# rw-directish-17mm-mk-1_6.net
KiCad netlist of a schematic drawn in EAGLE
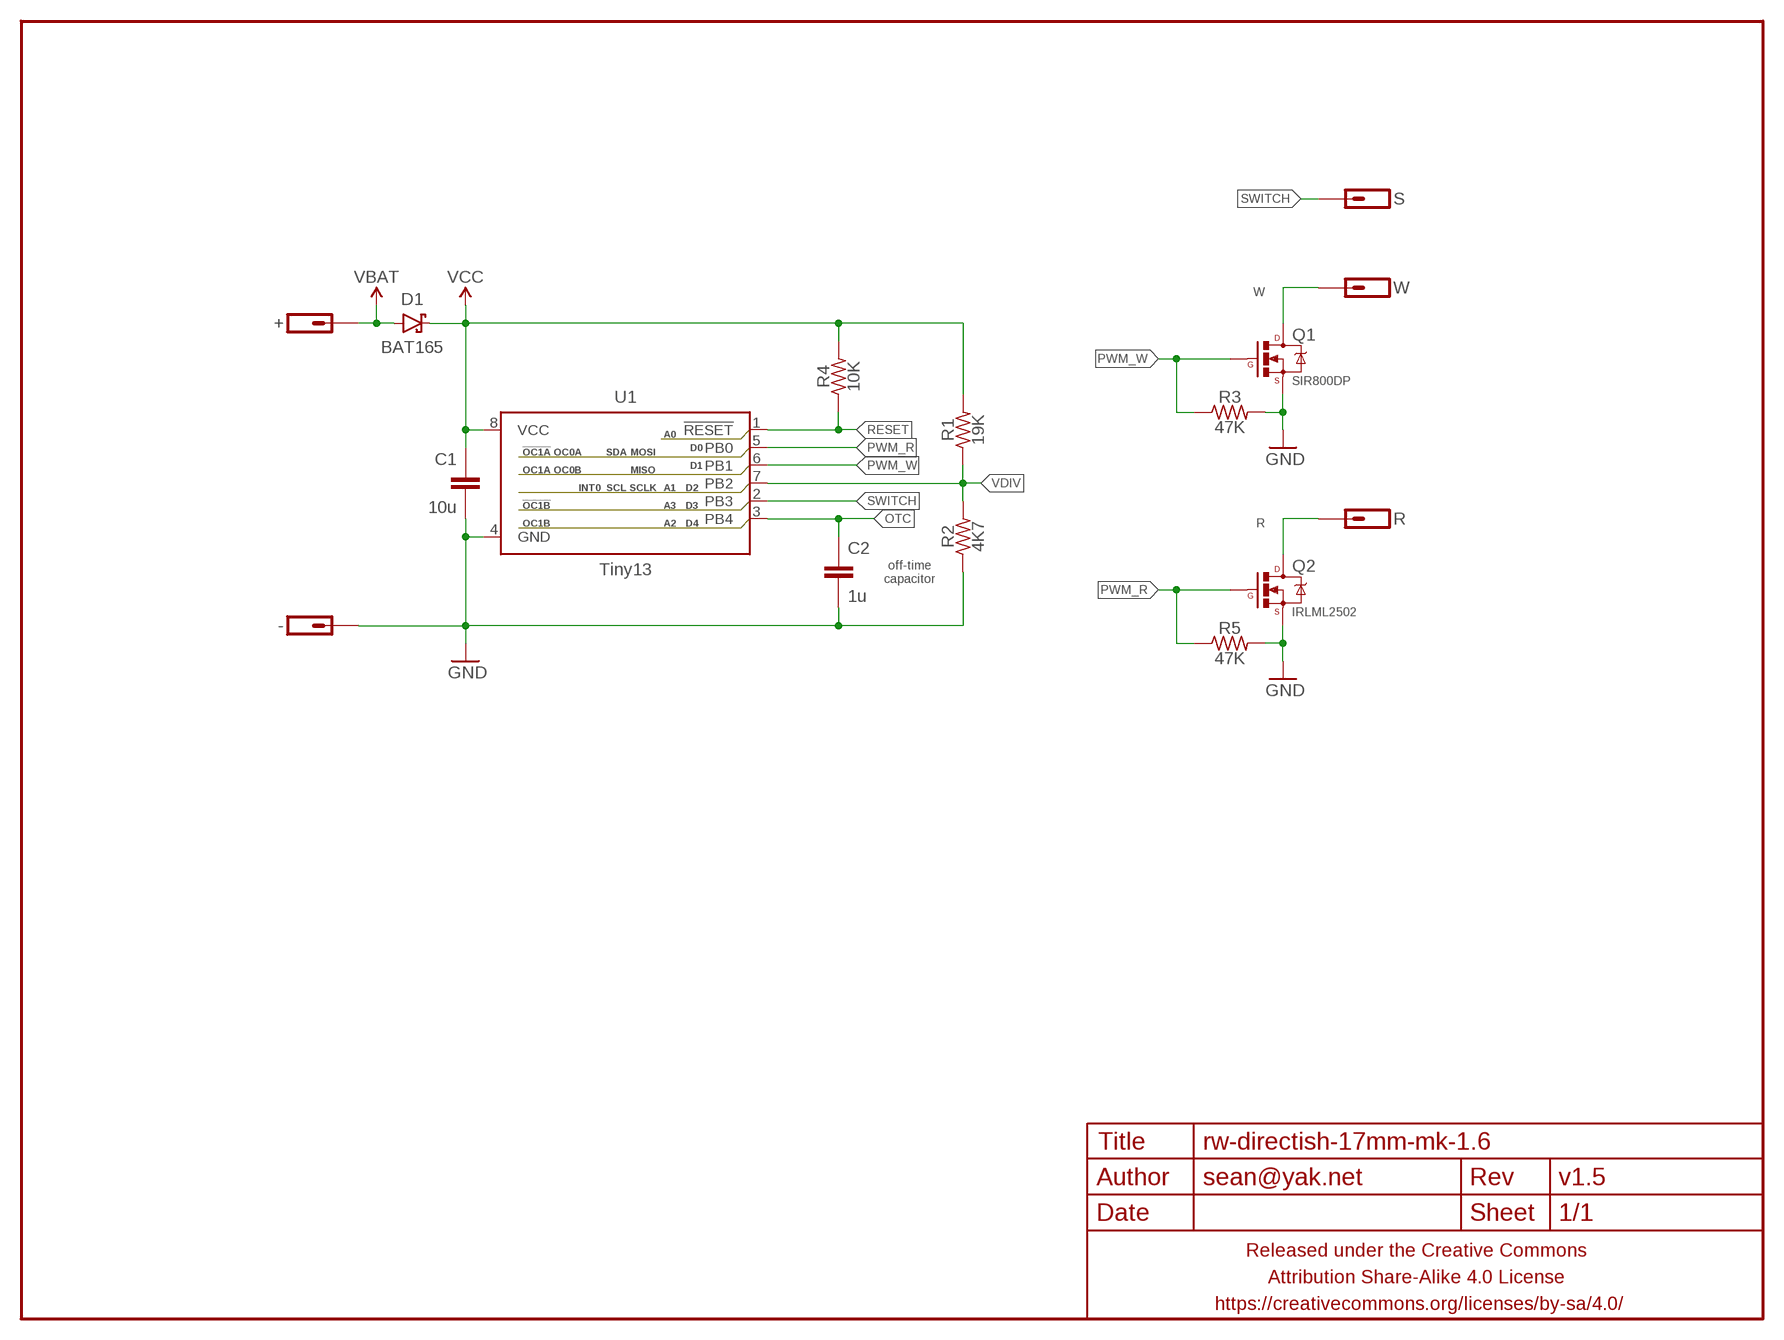
[diagram p0: schematic, sheet 1]

(export (version "E")
  (design (tool "Eeschema 10.0.6"))
  (components
    (comp (ref "+")
      (value "M01PTH-1MM-CIR-NS")
      (footprint "eagle-import:1X01-1MM-CIR-NS")
      (libsource (lib "eagle-import") (part "M01PTH-1MM-CIR-NS"))
    )
    (comp (ref "-")
      (value "M01NOT-A-VIA-NOPE")
      (footprint "eagle-import:1X01_NOSILK_NOSTOP")
      (libsource (lib "eagle-import") (part "M01NOT-A-VIA-NOPE"))
    )
    (comp (ref "C1")
      (value "10u")
      (footprint "eagle-import:C0603-TIGHTER")
      (libsource (lib "eagle-import") (part "CAPACITOR-CERAMICC0603-TIGHTER"))
    )
    (comp (ref "C2")
      (value "1u")
      (footprint "eagle-import:C0402")
      (libsource (lib "eagle-import") (part "CAPACITOR-CERAMICC0402"))
    )
    (comp (ref "D1")
      (value "BAT165")
      (footprint "eagle-import:SOD323-SCHOTTKY")
      (libsource (lib "eagle-import") (part "DIODE-SCHOTTKYSOD323"))
    )
    (comp (ref "FRAME1")
      (value "FRAME-LETTERNO_PACKAGE")
      (footprint "eagle-import:DUMMY")
      (fields (field (name "DESIGNER") "sean@yak.net") (field (name "VERSION") "v1.5"))
      (libsource (lib "eagle-import") (part "FRAME-LETTERNO_PACKAGE"))
    )
    (comp (ref "Q1")
      (value "SIR800DP")
      (footprint "eagle-import:POWERPACK-SO-8")
      (libsource (lib "eagle-import") (part "MOSFET-NCHANNELSIR800DP"))
    )
    (comp (ref "Q2")
      (value "IRLML2502")
      (footprint "eagle-import:SOT23-CLOSER")
      (libsource (lib "eagle-import") (part "MOSFET-NCHANNELIRLML2502-SMOL"))
    )
    (comp (ref "R")
      (value "M01SMD-1.25MM-DIA")
      (footprint "eagle-import:1X01-SMD-1.25MM-DIA-NS")
      (libsource (lib "eagle-import") (part "M01SMD-1.25MM-DIA"))
    )
    (comp (ref "R1")
      (value "19K")
      (footprint "eagle-import:R0402")
      (libsource (lib "eagle-import") (part "RESISTORR0402"))
    )
    (comp (ref "R2")
      (value "4K7")
      (footprint "eagle-import:R0402")
      (libsource (lib "eagle-import") (part "RESISTORR0402"))
    )
    (comp (ref "R3")
      (value "47K")
      (footprint "eagle-import:R0402")
      (libsource (lib "eagle-import") (part "RESISTORR0402"))
    )
    (comp (ref "R4")
      (value "10K")
      (footprint "eagle-import:R0402")
      (libsource (lib "eagle-import") (part "RESISTORR0402"))
    )
    (comp (ref "R5")
      (value "47K")
      (footprint "eagle-import:R0402")
      (libsource (lib "eagle-import") (part "RESISTORR0402"))
    )
    (comp (ref "S")
      (value "M01SMD-1.25MM-DIA")
      (footprint "eagle-import:1X01-SMD-1.25MM-DIA-NS")
      (libsource (lib "eagle-import") (part "M01SMD-1.25MM-DIA"))
    )
    (comp (ref "U1")
      (value "Tiny13")
      (footprint "eagle-import:SO08-NARROWER")
      (libsource (lib "eagle-import") (part "ATTINY13SOIC-NARROWPADS"))
    )
    (comp (ref "W")
      (value "M01NOSTOP-CANTSTOP-DONTKNOWHOWTOSTOP")
      (footprint "eagle-import:1X01_SMD_NOSTOP_NOSILK")
      (libsource (lib "eagle-import") (part "M01NOSTOP-CANTSTOP-DONTKNOWHOWTOSTOP"))
    )
  )
  (nets
    (net (code "1") (name "/R") (class "Default")
      (node (ref "Q2") (pin "3") (pinfunction "D_3") (pintype "passive"))
      (node (ref "R") (pin "P$1") (pinfunction "1_P$1") (pintype "passive"))
    )
    (net (code "2") (name "/W") (class "Default")
      (node (ref "Q1") (pin "5678") (pinfunction "D_5678") (pintype "passive"))
      (node (ref "W") (pin "1") (pinfunction "1_1") (pintype "passive"))
    )
    (net (code "3") (name "GND") (class "Default")
      (node (ref "-") (pin "P$1") (pinfunction "1_P$1") (pintype "passive"))
      (node (ref "C1") (pin "2") (pinfunction "2_2") (pintype "passive"))
      (node (ref "C2") (pin "2") (pinfunction "2_2") (pintype "passive"))
      (node (ref "Q1") (pin "1") (pinfunction "S_1") (pintype "passive"))
      (node (ref "Q1") (pin "2") (pinfunction "S_2") (pintype "passive"))
      (node (ref "Q1") (pin "3") (pinfunction "S_3") (pintype "passive"))
      (node (ref "Q2") (pin "2") (pinfunction "S_2") (pintype "passive"))
      (node (ref "R2") (pin "1") (pinfunction "1_1") (pintype "passive"))
      (node (ref "R3") (pin "2") (pinfunction "2_2") (pintype "passive"))
      (node (ref "R5") (pin "2") (pinfunction "2_2") (pintype "passive"))
      (node (ref "U1") (pin "4") (pinfunction "GND_4") (pintype "bidirectional"))
    )
    (net (code "4") (name "OTC") (class "Default")
      (node (ref "C2") (pin "1") (pinfunction "1_1") (pintype "passive"))
      (node (ref "U1") (pin "3") (pinfunction "PB4_3") (pintype "bidirectional"))
    )
    (net (code "5") (name "PWM_R") (class "Default")
      (node (ref "Q2") (pin "1") (pinfunction "G_1") (pintype "passive"))
      (node (ref "R5") (pin "1") (pinfunction "1_1") (pintype "passive"))
      (node (ref "U1") (pin "5") (pinfunction "PB0_5") (pintype "bidirectional"))
    )
    (net (code "6") (name "PWM_W") (class "Default")
      (node (ref "Q1") (pin "4") (pinfunction "G_4") (pintype "passive"))
      (node (ref "R3") (pin "1") (pinfunction "1_1") (pintype "passive"))
      (node (ref "U1") (pin "6") (pinfunction "PB1_6") (pintype "bidirectional"))
    )
    (net (code "7") (name "RESET") (class "Default")
      (node (ref "R4") (pin "1") (pinfunction "1_1") (pintype "passive"))
      (node (ref "U1") (pin "1") (pinfunction "~{RESET}_1") (pintype "bidirectional"))
    )
    (net (code "8") (name "SWITCH") (class "Default")
      (node (ref "S") (pin "P$1") (pinfunction "1_P$1") (pintype "passive"))
      (node (ref "U1") (pin "2") (pinfunction "PB3_2") (pintype "bidirectional"))
    )
    (net (code "9") (name "VBAT") (class "Default")
      (node (ref "+") (pin "1") (pinfunction "1_1") (pintype "passive"))
      (node (ref "D1") (pin "A") (pinfunction "A_A") (pintype "passive"))
    )
    (net (code "10") (name "VCC") (class "Default")
      (node (ref "C1") (pin "1") (pinfunction "1_1") (pintype "passive"))
      (node (ref "D1") (pin "C") (pinfunction "C_C") (pintype "passive"))
      (node (ref "R1") (pin "2") (pinfunction "2_2") (pintype "passive"))
      (node (ref "R4") (pin "2") (pinfunction "2_2") (pintype "passive"))
      (node (ref "U1") (pin "8") (pinfunction "VCC_8") (pintype "bidirectional"))
    )
    (net (code "11") (name "VDIV") (class "Default")
      (node (ref "R1") (pin "1") (pinfunction "1_1") (pintype "passive"))
      (node (ref "R2") (pin "2") (pinfunction "2_2") (pintype "passive"))
      (node (ref "U1") (pin "7") (pinfunction "PB2_7") (pintype "bidirectional"))
    )
  )
)
